# openSX70_WIP_NEW_LAYOUT_20171229_V30_man.net
KiCad netlist of a schematic drawn in EAGLE
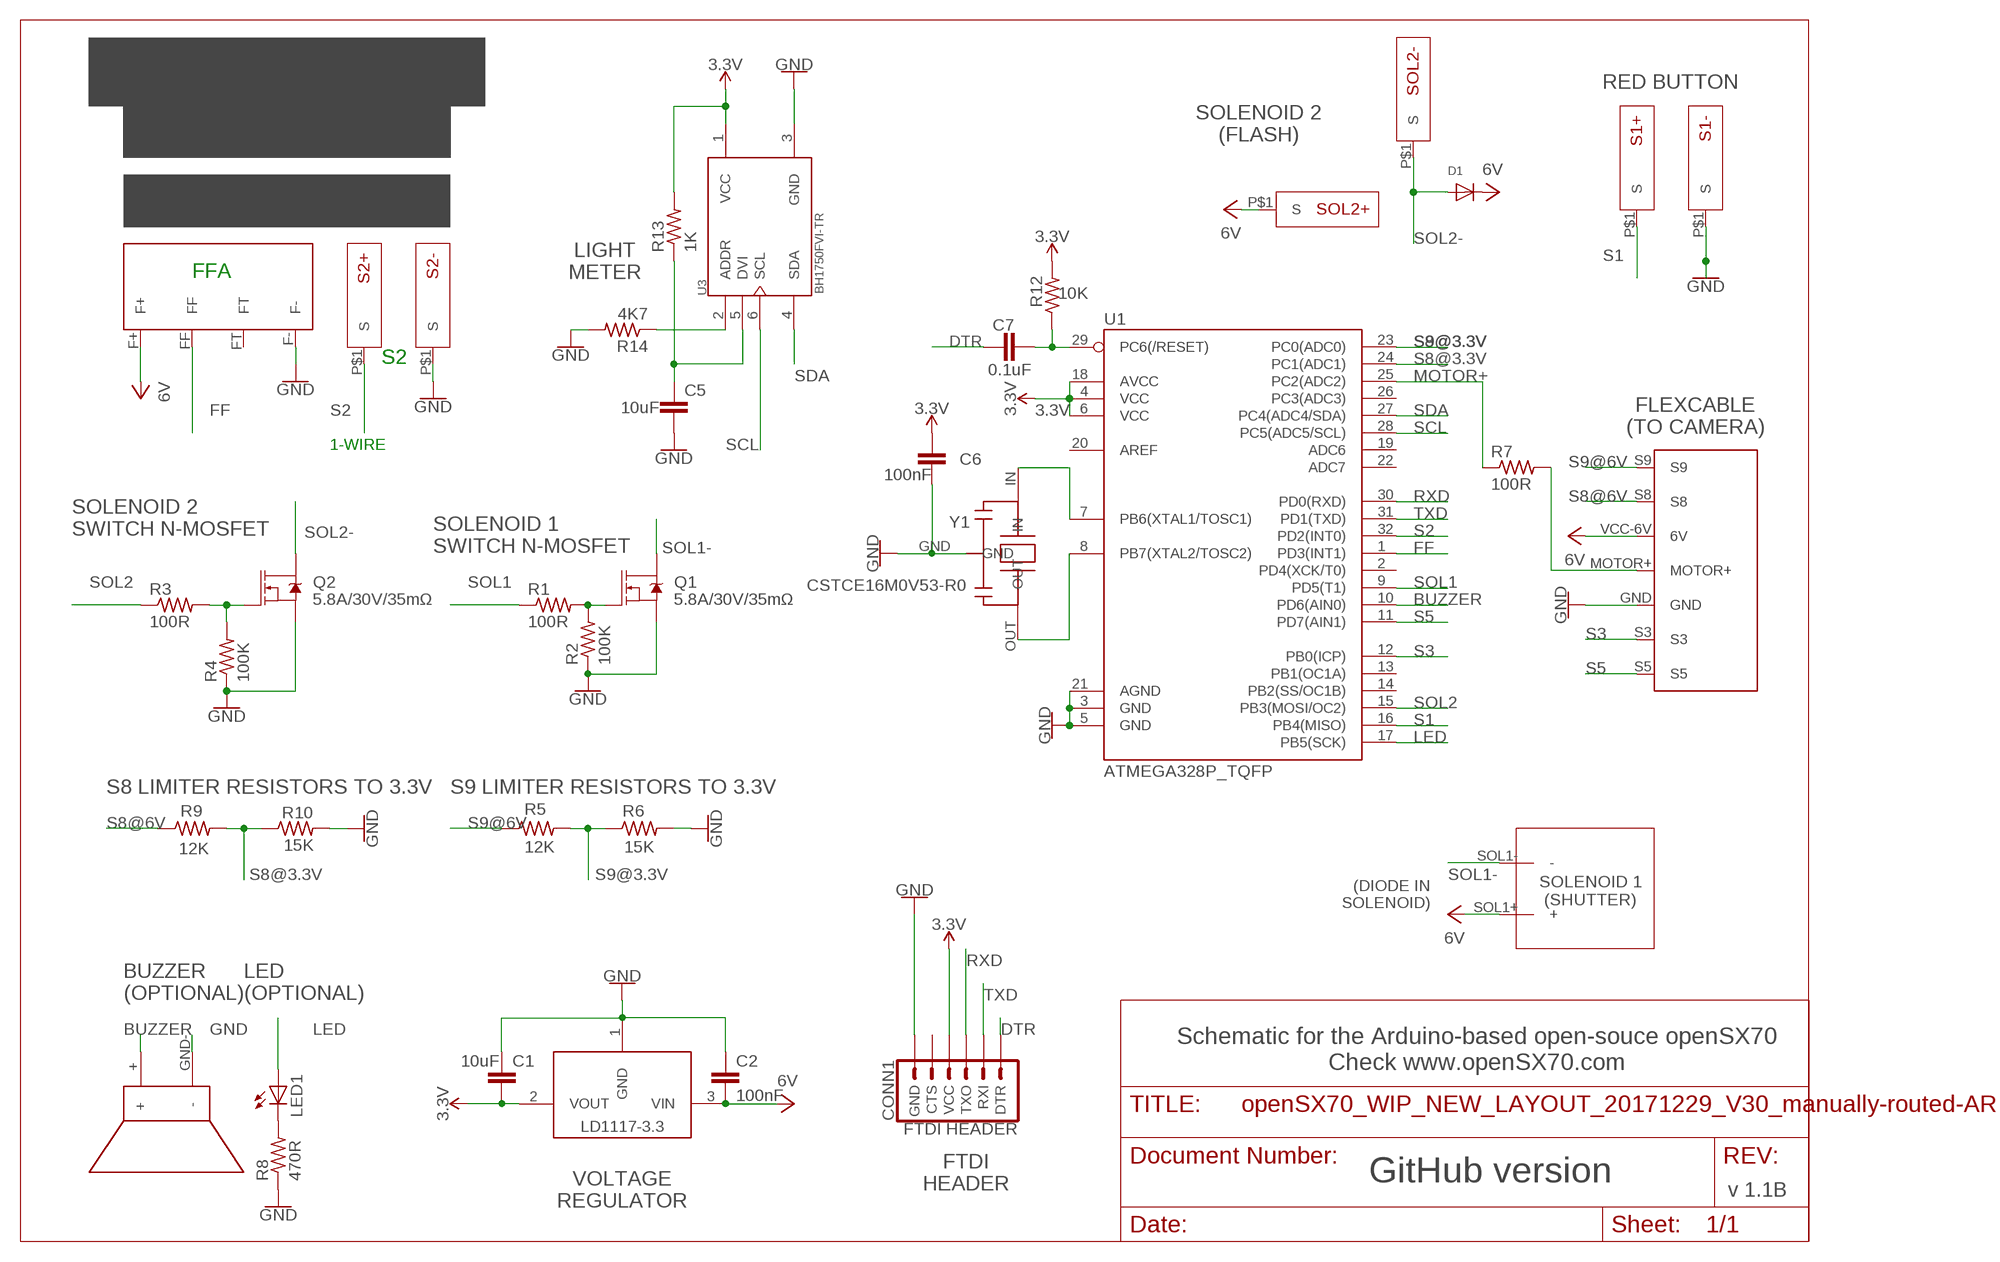
[diagram p0: schematic, sheet 1]

(export (version "E")
  (design (tool "Eeschema 10.0.6"))
  (components
    (comp (ref "BUZZ1")
      (value "CSET8-5G")
      (footprint "eagle-import:CSET8-5G_PACKAGE")
      (libsource (lib "eagle-import") (part "CSET8-5G"))
    )
    (comp (ref "C1")
      (value "10uF")
      (footprint "eagle-import:0603")
      (libsource (lib "eagle-import") (part "10UF-0603-6.3V-20%"))
    )
    (comp (ref "C2")
      (value "100nF")
      (footprint "eagle-import:C0603K")
      (libsource (lib "eagle-import") (part "C-EUC0603K"))
    )
    (comp (ref "C5")
      (value "10uF")
      (footprint "eagle-import:0603")
      (libsource (lib "eagle-import") (part "10UF-0603-6.3V-20%"))
    )
    (comp (ref "C6")
      (value "100nF")
      (footprint "eagle-import:C0805")
      (libsource (lib "eagle-import") (part "resistor_C-EUC0805"))
    )
    (comp (ref "C7")
      (value "0.1uF")
      (footprint "eagle-import:0603")
      (libsource (lib "eagle-import") (part "0.1UF-0603-25V-(+80/-20%)"))
    )
    (comp (ref "CONN1")
      (value "FTDI HEADER")
      (footprint "eagle-import:1X06")
      (libsource (lib "eagle-import") (part "6_PIN_SERIAL_TARGET"))
    )
    (comp (ref "D1")
      (value "DIODESOD-523")
      (footprint "eagle-import:SOD-523")
      (libsource (lib "eagle-import") (part "DIODESOD-523"))
    )
    (comp (ref "LD11173.3V")
      (value "LD1117 3.3V")
      (footprint "eagle-import:SOT223")
      (fields (field (name "MF") "Advanced Monolithic Systems") (field (name "MP") "AMS1117-5.0"))
      (libsource (lib "eagle-import") (part "LD1117-3.3"))
    )
    (comp (ref "LED1")
      (value "LEDCHIPLED_0805")
      (footprint "eagle-import:CHIPLED_0805")
      (libsource (lib "eagle-import") (part "LEDCHIPLED_0805"))
    )
    (comp (ref "Q1")
      (value "5.8A/30V/35mΩ")
      (footprint "eagle-import:SOT23-3")
      (libsource (lib "eagle-import") (part "MOSFET-NCH-AO3404A"))
    )
    (comp (ref "Q2")
      (value "5.8A/30V/35mΩ")
      (footprint "eagle-import:SOT23-3")
      (libsource (lib "eagle-import") (part "MOSFET-NCH-AO3404A"))
    )
    (comp (ref "R1")
      (value "100R")
      (footprint "eagle-import:R0603")
      (libsource (lib "eagle-import") (part "R-US_R0603"))
    )
    (comp (ref "R2")
      (value "100K")
      (footprint "eagle-import:R0603")
      (libsource (lib "eagle-import") (part "R-US_R0603"))
    )
    (comp (ref "R3")
      (value "100R")
      (footprint "eagle-import:R0603")
      (libsource (lib "eagle-import") (part "R-US_R0603"))
    )
    (comp (ref "R4")
      (value "100K")
      (footprint "eagle-import:R0603")
      (libsource (lib "eagle-import") (part "R-US_R0603"))
    )
    (comp (ref "R5")
      (value "12K")
      (footprint "eagle-import:R0603")
      (libsource (lib "eagle-import") (part "R-US_R0603"))
    )
    (comp (ref "R6")
      (value "15K")
      (footprint "eagle-import:R0603")
      (libsource (lib "eagle-import") (part "R-US_R0603"))
    )
    (comp (ref "R7")
      (value "100R")
      (footprint "eagle-import:R0603")
      (libsource (lib "eagle-import") (part "R-US_R0603"))
    )
    (comp (ref "R8")
      (value "470R")
      (footprint "eagle-import:R0603")
      (libsource (lib "eagle-import") (part "R-US_R0603"))
    )
    (comp (ref "R9")
      (value "12K")
      (footprint "eagle-import:R0603")
      (libsource (lib "eagle-import") (part "R-US_R0603"))
    )
    (comp (ref "R10")
      (value "15K")
      (footprint "eagle-import:R0603")
      (libsource (lib "eagle-import") (part "R-US_R0603"))
    )
    (comp (ref "R12")
      (value "10K")
      (footprint "eagle-import:R0603")
      (libsource (lib "eagle-import") (part "R-US_R0603"))
    )
    (comp (ref "R13")
      (value "1K")
      (footprint "eagle-import:R0603")
      (libsource (lib "eagle-import") (part "R-US_R0603"))
    )
    (comp (ref "R14")
      (value "4K7")
      (footprint "eagle-import:R0603")
      (libsource (lib "eagle-import") (part "R-US_R0603"))
    )
    (comp (ref "S1+")
      (value "SX70_S-PAD")
      (footprint "eagle-import:SX70-S-PAD")
      (libsource (lib "eagle-import") (part "SX70_S-PAD"))
    )
    (comp (ref "S1-")
      (value "SX70_S-PAD")
      (footprint "eagle-import:SX70-S-PAD")
      (libsource (lib "eagle-import") (part "SX70_S-PAD"))
    )
    (comp (ref "S2+")
      (value "SX70_S-PAD")
      (footprint "eagle-import:SX70-S-PAD")
      (libsource (lib "eagle-import") (part "SX70_S-PAD"))
    )
    (comp (ref "S2-")
      (value "SX70_S-PAD")
      (footprint "eagle-import:SX70-S-PAD")
      (libsource (lib "eagle-import") (part "SX70_S-PAD"))
    )
    (comp (ref "SOL1")
      (value "SX70-SOLENOID1-2PADS")
      (footprint "eagle-import:SX70-SOLENOID1-2")
      (libsource (lib "eagle-import") (part "SX70-SOLENOID1-2PADS"))
    )
    (comp (ref "SOL2+")
      (value "SX70_S-PAD")
      (footprint "eagle-import:SX70-S-PAD")
      (libsource (lib "eagle-import") (part "SX70_S-PAD"))
    )
    (comp (ref "SOL2-")
      (value "SX70_S-PAD")
      (footprint "eagle-import:SX70-S-PAD")
      (libsource (lib "eagle-import") (part "SX70_S-PAD"))
    )
    (comp (ref "U$1")
      (value "SX70-7-PAD")
      (footprint "eagle-import:SX70-7-PAD")
      (libsource (lib "eagle-import") (part "SX70-7-PAD"))
    )
    (comp (ref "U$2")
      (value "FFA")
      (footprint "eagle-import:FFA-PAD-PACKAGE")
      (libsource (lib "eagle-import") (part "SX70-FFA-PAD"))
    )
    (comp (ref "U1")
      (value "ATMEGA328P_TQFP")
      (footprint "eagle-import:TQFP32-08")
      (libsource (lib "eagle-import") (part "ATMEGA328P_TQFP"))
    )
    (comp (ref "U3")
      (value "BH1750FVI-TR")
      (footprint "eagle-import:SOTFL50P300X75-6N")
      (fields (field (name "MF") "Rohm"))
      (libsource (lib "eagle-import") (part "BH1750FVI-TR"))
    )
    (comp (ref "Y1")
      (value "CSTCE16M0V53-R0")
      (footprint "eagle-import:CFP95P160X100-3N")
      (fields (field (name "MF") "Murata"))
      (libsource (lib "eagle-import") (part "CSTCE16M0V53-R0"))
    )
  )
  (nets
    (net (code "1") (name "/BUZZER") (class "Default")
      (node (ref "BUZZ1") (pin "+") (pinfunction "+_+") (pintype "bidirectional"))
      (node (ref "U1") (pin "10") (pinfunction "PD6(AIN0)_10") (pintype "bidirectional"))
    )
    (net (code "2") (name "/DTR") (class "Default")
      (node (ref "C7") (pin "1") (pinfunction "1_1") (pintype "passive"))
      (node (ref "CONN1") (pin "1") (pinfunction "DTR_1") (pintype "passive"))
    )
    (net (code "3") (name "/FF") (class "Default")
      (node (ref "U$2") (pin "FF") (pinfunction "FF_FF") (pintype "bidirectional"))
      (node (ref "U1") (pin "1") (pinfunction "PD3(INT1)_1") (pintype "bidirectional"))
    )
    (net (code "4") (name "/LED") (class "Default")
      (node (ref "LED1") (pin "A") (pinfunction "A_A") (pintype "passive"))
      (node (ref "U1") (pin "17") (pinfunction "PB5(SCK)_17") (pintype "bidirectional"))
    )
    (net (code "5") (name "/MOTOR+") (class "Default")
      (node (ref "R7") (pin "1") (pinfunction "1_1") (pintype "passive"))
      (node (ref "U1") (pin "25") (pinfunction "PC2(ADC2)_25") (pintype "bidirectional"))
    )
    (net (code "6") (name "/RXD") (class "Default")
      (node (ref "CONN1") (pin "3") (pinfunction "TXO_3") (pintype "passive"))
      (node (ref "U1") (pin "30") (pinfunction "PD0(RXD)_30") (pintype "bidirectional"))
    )
    (net (code "7") (name "/S1") (class "Default")
      (node (ref "S1+") (pin "P$1") (pinfunction "S_P$1") (pintype "bidirectional"))
      (node (ref "U1") (pin "16") (pinfunction "PB4(MISO)_16") (pintype "bidirectional"))
    )
    (net (code "8") (name "/S2") (class "Default")
      (node (ref "S2+") (pin "P$1") (pinfunction "S_P$1") (pintype "bidirectional"))
      (node (ref "U1") (pin "32") (pinfunction "PD2(INT0)_32") (pintype "bidirectional"))
    )
    (net (code "9") (name "/S3") (class "Default")
      (node (ref "U$1") (pin "S3") (pinfunction "S3_S3") (pintype "bidirectional"))
      (node (ref "U1") (pin "12") (pinfunction "PB0(ICP)_12") (pintype "bidirectional"))
    )
    (net (code "10") (name "/S5") (class "Default")
      (node (ref "U$1") (pin "S5") (pinfunction "S5_S5") (pintype "bidirectional"))
      (node (ref "U1") (pin "11") (pinfunction "PD7(AIN1)_11") (pintype "bidirectional"))
    )
    (net (code "11") (name "/S8@3.3V") (class "Default")
      (node (ref "R10") (pin "1") (pinfunction "1_1") (pintype "passive"))
      (node (ref "R9") (pin "2") (pinfunction "2_2") (pintype "passive"))
      (node (ref "U1") (pin "24") (pinfunction "PC1(ADC1)_24") (pintype "bidirectional"))
    )
    (net (code "12") (name "/S8@6V") (class "Default")
      (node (ref "R9") (pin "1") (pinfunction "1_1") (pintype "passive"))
      (node (ref "U$1") (pin "S8") (pinfunction "S8_S8") (pintype "bidirectional"))
    )
    (net (code "13") (name "/S9@3.3V") (class "Default")
      (node (ref "R5") (pin "2") (pinfunction "2_2") (pintype "passive"))
      (node (ref "R6") (pin "1") (pinfunction "1_1") (pintype "passive"))
      (node (ref "U1") (pin "23") (pinfunction "PC0(ADC0)_23") (pintype "bidirectional"))
    )
    (net (code "14") (name "/S9@6V") (class "Default")
      (node (ref "R5") (pin "1") (pinfunction "1_1") (pintype "passive"))
      (node (ref "U$1") (pin "S9") (pinfunction "S9_S9") (pintype "bidirectional"))
    )
    (net (code "15") (name "/SCL") (class "Default")
      (node (ref "U1") (pin "28") (pinfunction "PC5(ADC5/SCL)_28") (pintype "bidirectional"))
      (node (ref "U3") (pin "6") (pinfunction "SCL_6") (pintype "input"))
    )
    (net (code "16") (name "/SDA") (class "Default")
      (node (ref "U1") (pin "27") (pinfunction "PC4(ADC4/SDA)_27") (pintype "bidirectional"))
      (node (ref "U3") (pin "4") (pinfunction "SDA_4") (pintype "bidirectional"))
    )
    (net (code "17") (name "/SOL1") (class "Default")
      (node (ref "R1") (pin "1") (pinfunction "1_1") (pintype "passive"))
      (node (ref "U1") (pin "9") (pinfunction "PD5(T1)_9") (pintype "bidirectional"))
    )
    (net (code "18") (name "/SOL1-") (class "Default")
      (node (ref "Q1") (pin "3") (pinfunction "D_3") (pintype "bidirectional"))
      (node (ref "SOL1") (pin "SOL1-") (pinfunction "-_SOL1-") (pintype "bidirectional"))
    )
    (net (code "19") (name "/SOL2") (class "Default")
      (node (ref "R3") (pin "1") (pinfunction "1_1") (pintype "passive"))
      (node (ref "U1") (pin "15") (pinfunction "PB3(MOSI/OC2)_15") (pintype "bidirectional"))
    )
    (net (code "20") (name "/SOL2-") (class "Default")
      (node (ref "D1") (pin "A") (pinfunction "A_A") (pintype "passive"))
      (node (ref "Q2") (pin "3") (pinfunction "D_3") (pintype "bidirectional"))
      (node (ref "SOL2-") (pin "P$1") (pinfunction "S_P$1") (pintype "bidirectional"))
    )
    (net (code "21") (name "/TXD") (class "Default")
      (node (ref "CONN1") (pin "2") (pinfunction "RXI_2") (pintype "passive"))
      (node (ref "U1") (pin "31") (pinfunction "PD1(TXD)_31") (pintype "bidirectional"))
    )
    (net (code "22") (name "3.3V") (class "Default")
      (node (ref "C1") (pin "2") (pinfunction "2_2") (pintype "passive"))
      (node (ref "C6") (pin "1") (pinfunction "1_1") (pintype "passive"))
      (node (ref "CONN1") (pin "4") (pinfunction "VCC_4") (pintype "passive"))
      (node (ref "LD11173.3V") (pin "2") (pinfunction "VOUT_2") (pintype "bidirectional"))
      (node (ref "R12") (pin "2") (pinfunction "2_2") (pintype "passive"))
      (node (ref "R13") (pin "2") (pinfunction "2_2") (pintype "passive"))
      (node (ref "U1") (pin "18") (pinfunction "AVCC_18") (pintype "bidirectional"))
      (node (ref "U1") (pin "4") (pinfunction "VCC_4") (pintype "bidirectional"))
      (node (ref "U1") (pin "6") (pinfunction "VCC_6") (pintype "bidirectional"))
      (node (ref "U3") (pin "1") (pinfunction "VCC_1") (pintype "power_in"))
    )
    (net (code "23") (name "6V") (class "Default")
      (node (ref "C2") (pin "2") (pinfunction "2_2") (pintype "passive"))
      (node (ref "D1") (pin "K") (pinfunction "C_K") (pintype "passive"))
      (node (ref "LD11173.3V") (pin "3") (pinfunction "VIN_3") (pintype "bidirectional"))
      (node (ref "SOL1") (pin "SOL1+") (pinfunction "+_SOL1+") (pintype "bidirectional"))
      (node (ref "SOL2+") (pin "P$1") (pinfunction "S_P$1") (pintype "bidirectional"))
      (node (ref "U$1") (pin "VCC-6V") (pinfunction "6V_VCC-6V") (pintype "bidirectional"))
      (node (ref "U$2") (pin "F+") (pinfunction "F+_F+") (pintype "bidirectional"))
    )
    (net (code "24") (name "GND") (class "Default")
      (node (ref "BUZZ1") (pin "GND-") (pinfunction "-_GND-") (pintype "bidirectional"))
      (node (ref "C1") (pin "1") (pinfunction "1_1") (pintype "passive"))
      (node (ref "C2") (pin "1") (pinfunction "1_1") (pintype "passive"))
      (node (ref "C5") (pin "2") (pinfunction "2_2") (pintype "passive"))
      (node (ref "C6") (pin "2") (pinfunction "2_2") (pintype "passive"))
      (node (ref "CONN1") (pin "6") (pinfunction "GND_6") (pintype "passive"))
      (node (ref "LD11173.3V") (pin "1") (pinfunction "GND_1") (pintype "bidirectional"))
      (node (ref "Q1") (pin "2") (pinfunction "S_2") (pintype "bidirectional"))
      (node (ref "Q2") (pin "2") (pinfunction "S_2") (pintype "bidirectional"))
      (node (ref "R10") (pin "2") (pinfunction "2_2") (pintype "passive"))
      (node (ref "R14") (pin "2") (pinfunction "2_2") (pintype "passive"))
      (node (ref "R2") (pin "1") (pinfunction "1_1") (pintype "passive"))
      (node (ref "R4") (pin "1") (pinfunction "1_1") (pintype "passive"))
      (node (ref "R6") (pin "2") (pinfunction "2_2") (pintype "passive"))
      (node (ref "R8") (pin "1") (pinfunction "1_1") (pintype "passive"))
      (node (ref "S1-") (pin "P$1") (pinfunction "S_P$1") (pintype "bidirectional"))
      (node (ref "S2-") (pin "P$1") (pinfunction "S_P$1") (pintype "bidirectional"))
      (node (ref "U$1") (pin "GND") (pinfunction "GND_GND") (pintype "bidirectional"))
      (node (ref "U$2") (pin "F-") (pinfunction "F-_F-") (pintype "bidirectional"))
      (node (ref "U1") (pin "21") (pinfunction "AGND_21") (pintype "bidirectional"))
      (node (ref "U1") (pin "3") (pinfunction "GND_3") (pintype "bidirectional"))
      (node (ref "U1") (pin "5") (pinfunction "GND_5") (pintype "bidirectional"))
      (node (ref "U3") (pin "3") (pinfunction "GND_3") (pintype "power_in"))
      (node (ref "Y1") (pin "GND") (pinfunction "GND_GND") (pintype "passive"))
    )
    (net (code "25") (name "Net-(LED1-PadC)") (class "Default")
      (node (ref "LED1") (pin "C") (pinfunction "C_C") (pintype "passive"))
      (node (ref "R8") (pin "2") (pinfunction "2_2") (pintype "passive"))
    )
    (net (code "26") (name "Net-(Q1-G)") (class "Default")
      (node (ref "Q1") (pin "1") (pinfunction "G_1") (pintype "bidirectional"))
      (node (ref "R1") (pin "2") (pinfunction "2_2") (pintype "passive"))
      (node (ref "R2") (pin "2") (pinfunction "2_2") (pintype "passive"))
    )
    (net (code "27") (name "Net-(Q2-G)") (class "Default")
      (node (ref "Q2") (pin "1") (pinfunction "G_1") (pintype "bidirectional"))
      (node (ref "R3") (pin "2") (pinfunction "2_2") (pintype "passive"))
      (node (ref "R4") (pin "2") (pinfunction "2_2") (pintype "passive"))
    )
    (net (code "28") (name "Net-(R7-Pad2)") (class "Default")
      (node (ref "R7") (pin "2") (pinfunction "2_2") (pintype "passive"))
      (node (ref "U$1") (pin "MOTOR+") (pinfunction "MOTOR+_MOTOR+") (pintype "bidirectional"))
    )
    (net (code "29") (name "Net-(U1-PB6(XTAL1{slash}TOSC1))") (class "Default")
      (node (ref "U1") (pin "7") (pinfunction "PB6(XTAL1/TOSC1)_7") (pintype "bidirectional"))
      (node (ref "Y1") (pin "IN") (pinfunction "IN_IN") (pintype "input"))
    )
    (net (code "30") (name "Net-(U1-PB7(XTAL2{slash}TOSC2))") (class "Default")
      (node (ref "U1") (pin "8") (pinfunction "PB7(XTAL2/TOSC2)_8") (pintype "bidirectional"))
      (node (ref "Y1") (pin "OUT") (pinfunction "OUT_OUT") (pintype "output"))
    )
    (net (code "31") (name "Net-(U1-PC6({slash}RESET))") (class "Default")
      (node (ref "C7") (pin "2") (pinfunction "2_2") (pintype "passive"))
      (node (ref "R12") (pin "1") (pinfunction "1_1") (pintype "passive"))
      (node (ref "U1") (pin "29") (pinfunction "PC6(/RESET)_29") (pintype "bidirectional"))
    )
    (net (code "32") (name "Net-(U3-ADDR)") (class "Default")
      (node (ref "R14") (pin "1") (pinfunction "1_1") (pintype "passive"))
      (node (ref "U3") (pin "2") (pinfunction "ADDR_2") (pintype "input"))
    )
    (net (code "33") (name "Net-(U3-DVI)") (class "Default")
      (node (ref "C5") (pin "1") (pinfunction "1_1") (pintype "passive"))
      (node (ref "R13") (pin "1") (pinfunction "1_1") (pintype "passive"))
      (node (ref "U3") (pin "5") (pinfunction "DVI_5") (pintype "input"))
    )
    (net (code "34") (name "unconnected-(CONN1-CTS-Pad5)") (class "Default")
      (node (ref "CONN1") (pin "5") (pinfunction "CTS_5") (pintype "passive"))
    )
    (net (code "35") (name "unconnected-(U$2-PadFT)") (class "Default")
      (node (ref "U$2") (pin "FT") (pinfunction "FT_FT") (pintype "bidirectional"))
    )
    (net (code "36") (name "unconnected-(U1-ADC6-Pad19)") (class "Default")
      (node (ref "U1") (pin "19") (pinfunction "ADC6_19") (pintype "bidirectional"))
    )
    (net (code "37") (name "unconnected-(U1-ADC7-Pad22)") (class "Default")
      (node (ref "U1") (pin "22") (pinfunction "ADC7_22") (pintype "bidirectional"))
    )
    (net (code "38") (name "unconnected-(U1-AREF-Pad20)") (class "Default")
      (node (ref "U1") (pin "20") (pinfunction "AREF_20") (pintype "bidirectional"))
    )
    (net (code "39") (name "unconnected-(U1-PB1(OC1A)-Pad13)") (class "Default")
      (node (ref "U1") (pin "13") (pinfunction "PB1(OC1A)_13") (pintype "bidirectional"))
    )
    (net (code "40") (name "unconnected-(U1-PB2(SS{slash}OC1B)-Pad14)") (class "Default")
      (node (ref "U1") (pin "14") (pinfunction "PB2(SS/OC1B)_14") (pintype "bidirectional"))
    )
    (net (code "41") (name "unconnected-(U1-PC3(ADC3)-Pad26)") (class "Default")
      (node (ref "U1") (pin "26") (pinfunction "PC3(ADC3)_26") (pintype "bidirectional"))
    )
    (net (code "42") (name "unconnected-(U1-PD4(XCK{slash}T0)-Pad2)") (class "Default")
      (node (ref "U1") (pin "2") (pinfunction "PD4(XCK/T0)_2") (pintype "bidirectional"))
    )
  )
)
